# APRS_module.net
KiCad netlist of a schematic drawn in EAGLE
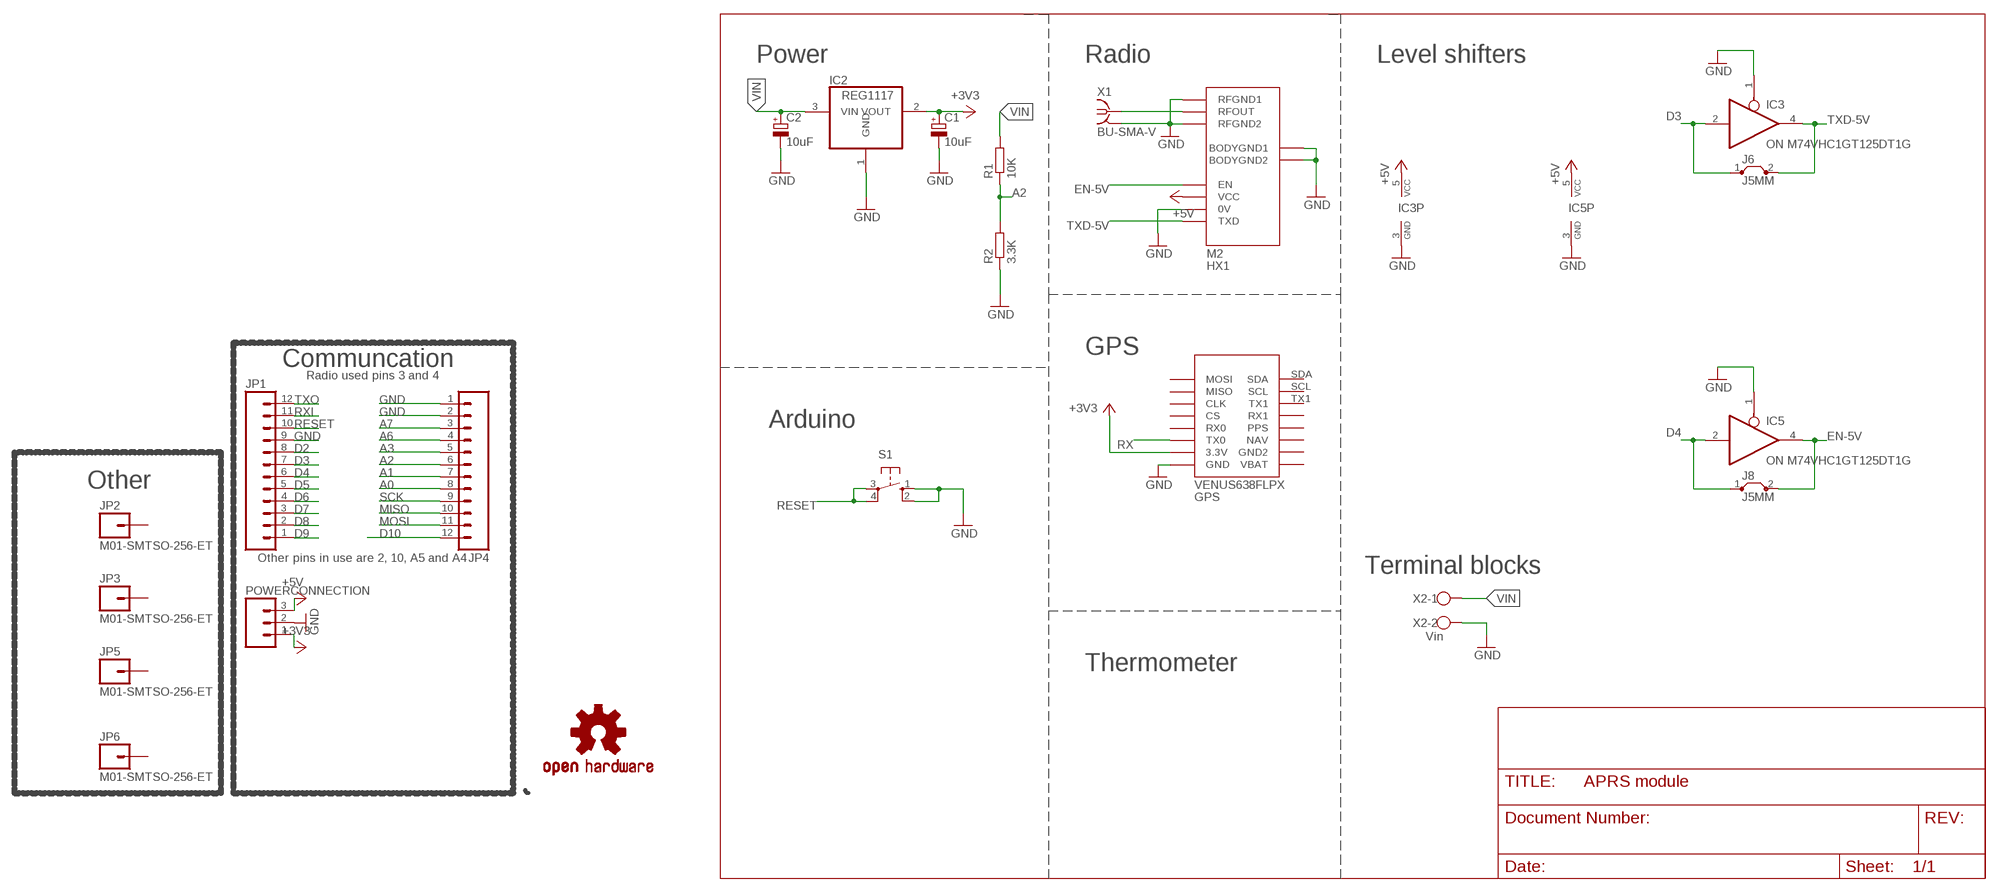
[diagram p0: schematic, sheet 1]

(export (version "E")
  (design (tool "Eeschema 10.0.6"))
  (components
    (comp (ref "C1")
      (value "10uF")
      (footprint "eagle-import:E2,5-5")
      (libsource (lib "eagle-import") (part "CPOL-EUE2.5-5"))
    )
    (comp (ref "C2")
      (value "10uF")
      (footprint "eagle-import:E2,5-5")
      (libsource (lib "eagle-import") (part "CPOL-EUE2.5-5"))
    )
    (comp (ref "GPS")
      (value "VENUS638FLPX")
      (footprint "eagle-import:VENUS638FLPX")
      (libsource (lib "eagle-import") (part "VENUS638FLPX"))
    )
    (comp (ref "IC2")
      (value "REG1117")
      (footprint "eagle-import:SOT223")
      (libsource (lib "eagle-import") (part "REG1117"))
    )
    (comp (ref "IC3")
      (value "ON M74VHC1GT125DT1G")
      (footprint "eagle-import:SOT23-5")
      (libsource (lib "eagle-import") (part "741G125DBVAHC"))
    )
    (comp (ref "IC5")
      (value "ON M74VHC1GT125DT1G")
      (footprint "eagle-import:SOT23-5")
      (libsource (lib "eagle-import") (part "741G125DBVAHC"))
    )
    (comp (ref "J6")
      (value "J5MM")
      (footprint "eagle-import:05")
      (libsource (lib "eagle-import") (part "J5MM"))
    )
    (comp (ref "J8")
      (value "J5MM")
      (footprint "eagle-import:05")
      (libsource (lib "eagle-import") (part "J5MM"))
    )
    (comp (ref "JP1")
      (value "M12PTH")
      (footprint "eagle-import:1X12")
      (libsource (lib "eagle-import") (part "M12PTH"))
    )
    (comp (ref "JP2")
      (value "M01-SMTSO-256-ET")
      (footprint "eagle-import:SMTSO-256-ET")
      (libsource (lib "eagle-import") (part "M01-SMTSO-256-ET"))
    )
    (comp (ref "JP3")
      (value "M01-SMTSO-256-ET")
      (footprint "eagle-import:SMTSO-256-ET")
      (libsource (lib "eagle-import") (part "M01-SMTSO-256-ET"))
    )
    (comp (ref "JP4")
      (value "M12PTH")
      (footprint "eagle-import:1X12")
      (libsource (lib "eagle-import") (part "M12PTH"))
    )
    (comp (ref "JP5")
      (value "M01-SMTSO-256-ET")
      (footprint "eagle-import:SMTSO-256-ET")
      (libsource (lib "eagle-import") (part "M01-SMTSO-256-ET"))
    )
    (comp (ref "JP6")
      (value "M01-SMTSO-256-ET")
      (footprint "eagle-import:SMTSO-256-ET")
      (libsource (lib "eagle-import") (part "M01-SMTSO-256-ET"))
    )
    (comp (ref "LOGO1")
      (value "OSHW-LOGOL")
      (footprint "eagle-import:OSHW-LOGO-L")
      (libsource (lib "eagle-import") (part "OSHW-LOGOL"))
    )
    (comp (ref "M2")
      (value "HX1")
      (footprint "eagle-import:HX1")
      (libsource (lib "eagle-import") (part "HX1"))
    )
    (comp (ref "POWERCONNECTION")
      (value "M03PTH")
      (footprint "eagle-import:1X03")
      (libsource (lib "eagle-import") (part "M03PTH"))
    )
    (comp (ref "R1")
      (value "10K")
      (footprint "eagle-import:R1206")
      (libsource (lib "eagle-import") (part "R-EU_R1206"))
    )
    (comp (ref "R2")
      (value "3.3K")
      (footprint "eagle-import:R1206")
      (libsource (lib "eagle-import") (part "R-EU_R1206"))
    )
    (comp (ref "S1")
      (value "10-XX")
      (footprint "eagle-import:B3F-10XX")
      (libsource (lib "eagle-import") (part "10-XX"))
    )
    (comp (ref "X1")
      (value "BU-SMA-V")
      (footprint "eagle-import:BU-SMA-V")
      (libsource (lib "eagle-import") (part "BU-SMA-V"))
    )
    (comp (ref "X2")
      (value "Vin")
      (footprint "eagle-import:W237-102")
      (fields (field (name "MPN") "237-102"))
      (libsource (lib "eagle-import") (part "W237-102"))
    )
  )
  (nets
    (net (code "1") (name "+3V3") (class "Default")
      (node (ref "C1") (pin "+") (pinfunction "+_+") (pintype "passive"))
      (node (ref "GPS") (pin "3.3V") (pinfunction "3.3V_3.3V") (pintype "bidirectional"))
      (node (ref "IC2") (pin "2") (pinfunction "VOUT_2") (pintype "output"))
      (node (ref "POWERCONNECTION") (pin "1") (pinfunction "1_1") (pintype "passive"))
    )
    (net (code "2") (name "+5V") (class "Default")
      (node (ref "IC3") (pin "5") (pinfunction "VCC_5") (pintype "power_in"))
      (node (ref "IC5") (pin "5") (pinfunction "VCC_5") (pintype "power_in"))
      (node (ref "M2") (pin "VCC") (pinfunction "VCC_VCC") (pintype "bidirectional"))
      (node (ref "POWERCONNECTION") (pin "3") (pinfunction "3_3") (pintype "passive"))
    )
    (net (code "3") (name "/A0") (class "Default")
      (node (ref "JP4") (pin "8") (pinfunction "8_8") (pintype "passive"))
    )
    (net (code "4") (name "/A1") (class "Default")
      (node (ref "JP4") (pin "7") (pinfunction "7_7") (pintype "passive"))
    )
    (net (code "5") (name "/A2") (class "Default")
      (node (ref "JP4") (pin "6") (pinfunction "6_6") (pintype "passive"))
      (node (ref "R1") (pin "1") (pinfunction "1_1") (pintype "passive"))
      (node (ref "R2") (pin "2") (pinfunction "2_2") (pintype "passive"))
    )
    (net (code "6") (name "/A3") (class "Default")
      (node (ref "JP4") (pin "5") (pinfunction "5_5") (pintype "passive"))
    )
    (net (code "7") (name "/A6") (class "Default")
      (node (ref "JP4") (pin "4") (pinfunction "4_4") (pintype "passive"))
    )
    (net (code "8") (name "/A7") (class "Default")
      (node (ref "JP4") (pin "3") (pinfunction "3_3") (pintype "passive"))
    )
    (net (code "9") (name "/D2") (class "Default")
      (node (ref "JP1") (pin "8") (pinfunction "8_8") (pintype "passive"))
    )
    (net (code "10") (name "/D3") (class "Default")
      (node (ref "IC3") (pin "2") (pinfunction "I_2") (pintype "input"))
      (node (ref "J6") (pin "1") (pinfunction "1_1") (pintype "passive"))
      (node (ref "JP1") (pin "7") (pinfunction "7_7") (pintype "passive"))
    )
    (net (code "11") (name "/D4") (class "Default")
      (node (ref "IC5") (pin "2") (pinfunction "I_2") (pintype "input"))
      (node (ref "J8") (pin "1") (pinfunction "1_1") (pintype "passive"))
      (node (ref "JP1") (pin "6") (pinfunction "6_6") (pintype "passive"))
    )
    (net (code "12") (name "/D5") (class "Default")
      (node (ref "JP1") (pin "5") (pinfunction "5_5") (pintype "passive"))
    )
    (net (code "13") (name "/D6") (class "Default")
      (node (ref "JP1") (pin "4") (pinfunction "4_4") (pintype "passive"))
    )
    (net (code "14") (name "/D7") (class "Default")
      (node (ref "JP1") (pin "3") (pinfunction "3_3") (pintype "passive"))
    )
    (net (code "15") (name "/D8") (class "Default")
      (node (ref "JP1") (pin "2") (pinfunction "2_2") (pintype "passive"))
    )
    (net (code "16") (name "/D9") (class "Default")
      (node (ref "JP1") (pin "1") (pinfunction "1_1") (pintype "passive"))
    )
    (net (code "17") (name "/D10") (class "Default")
      (node (ref "JP4") (pin "12") (pinfunction "12_12") (pintype "passive"))
    )
    (net (code "18") (name "/EN-5V") (class "Default")
      (node (ref "IC5") (pin "4") (pinfunction "O_4") (pintype "tri_state"))
      (node (ref "J8") (pin "2") (pinfunction "2_2") (pintype "passive"))
      (node (ref "M2") (pin "EN") (pinfunction "EN_EN") (pintype "bidirectional"))
    )
    (net (code "19") (name "/MISO") (class "Default")
      (node (ref "JP4") (pin "10") (pinfunction "10_10") (pintype "passive"))
    )
    (net (code "20") (name "/MOSI") (class "Default")
      (node (ref "JP4") (pin "11") (pinfunction "11_11") (pintype "passive"))
    )
    (net (code "21") (name "/RESET") (class "Default")
      (node (ref "JP1") (pin "10") (pinfunction "10_10") (pintype "passive"))
      (node (ref "S1") (pin "3") (pinfunction "P_3") (pintype "passive"))
      (node (ref "S1") (pin "4") (pinfunction "P1_4") (pintype "passive"))
    )
    (net (code "22") (name "/RX") (class "Default")
      (node (ref "GPS") (pin "TX0") (pinfunction "TX0_TX0") (pintype "bidirectional"))
    )
    (net (code "23") (name "/RXI") (class "Default")
      (node (ref "JP1") (pin "11") (pinfunction "11_11") (pintype "passive"))
    )
    (net (code "24") (name "/SCK") (class "Default")
      (node (ref "JP4") (pin "9") (pinfunction "9_9") (pintype "passive"))
    )
    (net (code "25") (name "/TXD-5V") (class "Default")
      (node (ref "IC3") (pin "4") (pinfunction "O_4") (pintype "tri_state"))
      (node (ref "J6") (pin "2") (pinfunction "2_2") (pintype "passive"))
      (node (ref "M2") (pin "TXD") (pinfunction "TXD_TXD") (pintype "bidirectional"))
    )
    (net (code "26") (name "/TXO") (class "Default")
      (node (ref "JP1") (pin "12") (pinfunction "12_12") (pintype "passive"))
    )
    (net (code "27") (name "GND") (class "Default")
      (node (ref "C1") (pin "-") (pinfunction "-_-") (pintype "passive"))
      (node (ref "C2") (pin "-") (pinfunction "-_-") (pintype "passive"))
      (node (ref "GPS") (pin "GND") (pinfunction "GND_GND") (pintype "bidirectional"))
      (node (ref "IC2") (pin "1") (pinfunction "GND_1") (pintype "power_in"))
      (node (ref "IC3") (pin "1") (pinfunction "OE_1") (pintype "input"))
      (node (ref "IC3") (pin "3") (pinfunction "GND_3") (pintype "power_in"))
      (node (ref "IC5") (pin "1") (pinfunction "OE_1") (pintype "input"))
      (node (ref "IC5") (pin "3") (pinfunction "GND_3") (pintype "power_in"))
      (node (ref "JP1") (pin "9") (pinfunction "9_9") (pintype "passive"))
      (node (ref "JP4") (pin "1") (pinfunction "1_1") (pintype "passive"))
      (node (ref "JP4") (pin "2") (pinfunction "2_2") (pintype "passive"))
      (node (ref "M2") (pin "0V") (pinfunction "0V_0V") (pintype "bidirectional"))
      (node (ref "M2") (pin "BODYGND1") (pinfunction "BODYGND1_BODYGND1") (pintype "bidirectional"))
      (node (ref "M2") (pin "BODYGND2") (pinfunction "BODYGND2_BODYGND2") (pintype "bidirectional"))
      (node (ref "M2") (pin "RFGND1") (pinfunction "RFGND1_RFGND1") (pintype "bidirectional"))
      (node (ref "M2") (pin "RFGND2") (pinfunction "RFGND2_RFGND2") (pintype "bidirectional"))
      (node (ref "POWERCONNECTION") (pin "2") (pinfunction "2_2") (pintype "passive"))
      (node (ref "R2") (pin "1") (pinfunction "1_1") (pintype "passive"))
      (node (ref "S1") (pin "1") (pinfunction "S_1") (pintype "passive"))
      (node (ref "S1") (pin "2") (pinfunction "S1_2") (pintype "passive"))
      (node (ref "X1") (pin "2") (pinfunction "GND_2") (pintype "power_in"))
      (node (ref "X2") (pin "2") (pinfunction "KL_2") (pintype "passive"))
    )
    (net (code "28") (name "Net-(M2-PadRFOUT)") (class "Default")
      (node (ref "M2") (pin "RFOUT") (pinfunction "RFOUT_RFOUT") (pintype "bidirectional"))
      (node (ref "X1") (pin "1") (pinfunction "1_1") (pintype "passive"))
    )
    (net (code "29") (name "VIN") (class "Default")
      (node (ref "C2") (pin "+") (pinfunction "+_+") (pintype "passive"))
      (node (ref "IC2") (pin "3") (pinfunction "VIN_3") (pintype "input"))
      (node (ref "R1") (pin "2") (pinfunction "2_2") (pintype "passive"))
      (node (ref "X2") (pin "1") (pinfunction "KL_1") (pintype "passive"))
    )
    (net (code "30") (name "unconnected-(GPS-PadCLK)") (class "Default")
      (node (ref "GPS") (pin "CLK") (pinfunction "CLK_CLK") (pintype "bidirectional"))
    )
    (net (code "31") (name "unconnected-(GPS-PadCS)") (class "Default")
      (node (ref "GPS") (pin "CS") (pinfunction "CS_CS") (pintype "bidirectional"))
    )
    (net (code "32") (name "unconnected-(GPS-PadGND2)") (class "Default")
      (node (ref "GPS") (pin "GND2") (pinfunction "GND2_GND2") (pintype "bidirectional"))
    )
    (net (code "33") (name "unconnected-(GPS-PadMISO)") (class "Default")
      (node (ref "GPS") (pin "MISO") (pinfunction "MISO_MISO") (pintype "bidirectional"))
    )
    (net (code "34") (name "unconnected-(GPS-PadMOSI)") (class "Default")
      (node (ref "GPS") (pin "MOSI") (pinfunction "MOSI_MOSI") (pintype "bidirectional"))
    )
    (net (code "35") (name "unconnected-(GPS-PadNAV)") (class "Default")
      (node (ref "GPS") (pin "NAV") (pinfunction "NAV_NAV") (pintype "bidirectional"))
    )
    (net (code "36") (name "unconnected-(GPS-PadPPS)") (class "Default")
      (node (ref "GPS") (pin "PPS") (pinfunction "PPS_PPS") (pintype "bidirectional"))
    )
    (net (code "37") (name "unconnected-(GPS-PadRX0)") (class "Default")
      (node (ref "GPS") (pin "RX0") (pinfunction "RX0_RX0") (pintype "bidirectional"))
    )
    (net (code "38") (name "unconnected-(GPS-PadRX1)") (class "Default")
      (node (ref "GPS") (pin "RX1") (pinfunction "RX1_RX1") (pintype "bidirectional"))
    )
    (net (code "39") (name "unconnected-(GPS-PadSCL)") (class "Default")
      (node (ref "GPS") (pin "SCL") (pinfunction "SCL_SCL") (pintype "bidirectional"))
    )
    (net (code "40") (name "unconnected-(GPS-PadSDA)") (class "Default")
      (node (ref "GPS") (pin "SDA") (pinfunction "SDA_SDA") (pintype "bidirectional"))
    )
    (net (code "41") (name "unconnected-(GPS-PadTX1)") (class "Default")
      (node (ref "GPS") (pin "TX1") (pinfunction "TX1_TX1") (pintype "bidirectional"))
    )
    (net (code "42") (name "unconnected-(GPS-PadVBAT)") (class "Default")
      (node (ref "GPS") (pin "VBAT") (pinfunction "VBAT_VBAT") (pintype "bidirectional"))
    )
    (net (code "43") (name "unconnected-(JP2-1-PadP$1)") (class "Default")
      (node (ref "JP2") (pin "P$1") (pinfunction "1_P$1") (pintype "passive"))
    )
    (net (code "44") (name "unconnected-(JP3-1-PadP$1)") (class "Default")
      (node (ref "JP3") (pin "P$1") (pinfunction "1_P$1") (pintype "passive"))
    )
    (net (code "45") (name "unconnected-(JP5-1-PadP$1)") (class "Default")
      (node (ref "JP5") (pin "P$1") (pinfunction "1_P$1") (pintype "passive"))
    )
    (net (code "46") (name "unconnected-(JP6-1-PadP$1)") (class "Default")
      (node (ref "JP6") (pin "P$1") (pinfunction "1_P$1") (pintype "passive"))
    )
  )
)
